# BIRDS-5_FM_-X_Panel_Ver2.net
KiCad netlist of a schematic drawn in EAGLE
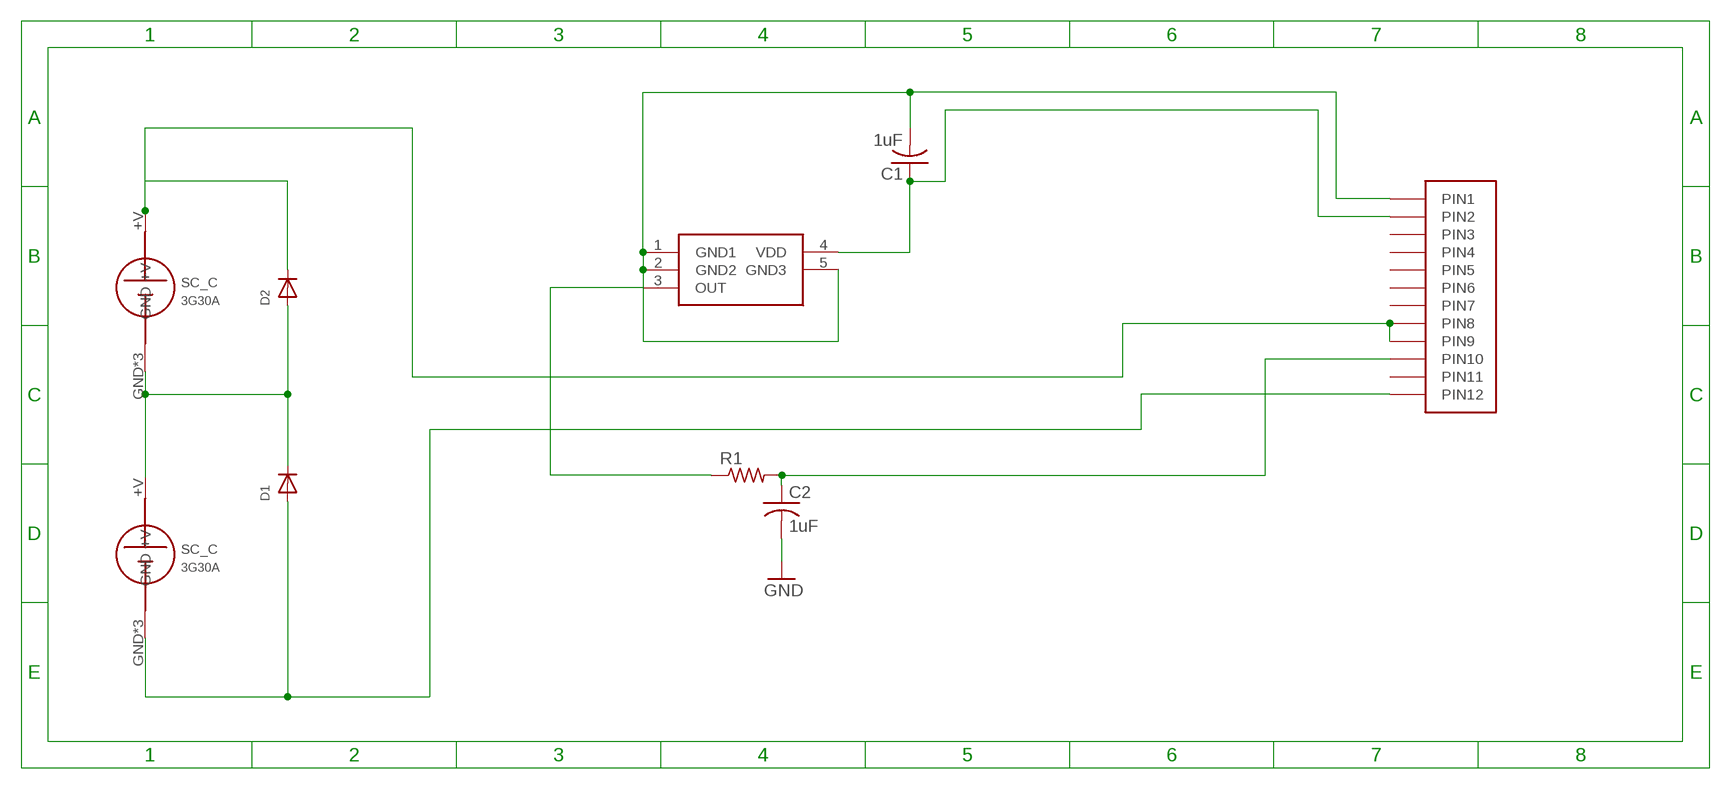
[diagram p0: schematic, sheet 1]

(export (version "E")
  (design (tool "Eeschema 10.0.6"))
  (components
    (comp (ref "C1")
      (value "1uF")
      (footprint "eagle-import:C0805")
      (libsource (lib "eagle-import") (part "C-USC0805"))
    )
    (comp (ref "C2")
      (value "1uF")
      (footprint "eagle-import:C0805")
      (libsource (lib "eagle-import") (part "C-USC0805"))
    )
    (comp (ref "D1")
      (value "DIODE_SOD-123FL")
      (footprint "eagle-import:SOD-123FL")
      (libsource (lib "eagle-import") (part "DIODE_SOD-123FL"))
    )
    (comp (ref "D2")
      (value "DIODE_SOD-123FL")
      (footprint "eagle-import:SOD-123FL")
      (libsource (lib "eagle-import") (part "DIODE_SOD-123FL"))
    )
    (comp (ref "R1")
      (value "R-US_R0402")
      (footprint "eagle-import:R0402")
      (libsource (lib "eagle-import") (part "R-US_R0402"))
    )
    (comp (ref "U$1")
      (value "HEADER12PIN")
      (footprint "eagle-import:HEADER12PIN")
      (libsource (lib "eagle-import") (part "HEADER12PIN"))
    )
    (comp (ref "U$3")
      (value "LMT84DCKT")
      (footprint "eagle-import:SOT65P210X110-5N")
      (fields (field (name "RS_PART_NUMBER") "8115860"))
      (libsource (lib "eagle-import") (part "LMT84DCKT"))
    )
    (comp (ref "U$4")
      (value "SC_C")
      (footprint "eagle-import:SC_C")
      (libsource (lib "eagle-import") (part "SC_C"))
    )
    (comp (ref "U$5")
      (value "SC_C")
      (footprint "eagle-import:SC_C")
      (libsource (lib "eagle-import") (part "SC_C"))
    )
  )
  (nets
    (net (code "1") (name "GND") (class "Default")
      (node (ref "C1") (pin "2") (pinfunction "2_2") (pintype "passive"))
      (node (ref "C2") (pin "2") (pinfunction "2_2") (pintype "passive"))
      (node (ref "D1") (pin "A") (pinfunction "A_A") (pintype "passive"))
      (node (ref "U$1") (pin "P1") (pinfunction "PIN1_P1") (pintype "bidirectional"))
      (node (ref "U$1") (pin "P12") (pinfunction "PIN12_P12") (pintype "bidirectional"))
      (node (ref "U$3") (pin "1") (pinfunction "GND1_1") (pintype "power_in"))
      (node (ref "U$3") (pin "2") (pinfunction "GND2_2") (pintype "power_in"))
      (node (ref "U$3") (pin "5") (pinfunction "GND3_5") (pintype "power_in"))
      (node (ref "U$5") (pin "GND") (pinfunction "GND_GND") (pintype "bidirectional"))
      (node (ref "U$5") (pin "GND1") (pinfunction "GND_GND1") (pintype "bidirectional"))
      (node (ref "U$5") (pin "GND2") (pinfunction "GND_GND2") (pintype "bidirectional"))
    )
    (net (code "2") (name "Net-(D1-PadC)") (class "Default")
      (node (ref "D1") (pin "C") (pinfunction "C_C") (pintype "passive"))
      (node (ref "D2") (pin "A") (pinfunction "A_A") (pintype "passive"))
      (node (ref "U$4") (pin "GND") (pinfunction "GND_GND") (pintype "bidirectional"))
      (node (ref "U$4") (pin "GND1") (pinfunction "GND_GND1") (pintype "bidirectional"))
      (node (ref "U$4") (pin "GND2") (pinfunction "GND_GND2") (pintype "bidirectional"))
      (node (ref "U$5") (pin "+V") (pinfunction "+V_+V") (pintype "bidirectional"))
    )
    (net (code "3") (name "Net-(U$1-PIN2)") (class "Default")
      (node (ref "C1") (pin "1") (pinfunction "1_1") (pintype "passive"))
      (node (ref "U$1") (pin "P2") (pinfunction "PIN2_P2") (pintype "bidirectional"))
      (node (ref "U$3") (pin "4") (pinfunction "VDD_4") (pintype "power_in"))
    )
    (net (code "4") (name "Net-(U$1-PIN8)") (class "Default")
      (node (ref "D2") (pin "C") (pinfunction "C_C") (pintype "passive"))
      (node (ref "U$1") (pin "P8") (pinfunction "PIN8_P8") (pintype "bidirectional"))
      (node (ref "U$1") (pin "P9") (pinfunction "PIN9_P9") (pintype "bidirectional"))
      (node (ref "U$4") (pin "+V") (pinfunction "+V_+V") (pintype "bidirectional"))
    )
    (net (code "5") (name "Net-(U$1-PIN10)") (class "Default")
      (node (ref "C2") (pin "1") (pinfunction "1_1") (pintype "passive"))
      (node (ref "R1") (pin "2") (pinfunction "2_2") (pintype "passive"))
      (node (ref "U$1") (pin "P10") (pinfunction "PIN10_P10") (pintype "bidirectional"))
    )
    (net (code "6") (name "Net-(U$3-OUT)") (class "Default")
      (node (ref "R1") (pin "1") (pinfunction "1_1") (pintype "passive"))
      (node (ref "U$3") (pin "3") (pinfunction "OUT_3") (pintype "output"))
    )
    (net (code "7") (name "unconnected-(U$1-PIN3-PadP3)") (class "Default")
      (node (ref "U$1") (pin "P3") (pinfunction "PIN3_P3") (pintype "bidirectional"))
    )
    (net (code "8") (name "unconnected-(U$1-PIN4-PadP4)") (class "Default")
      (node (ref "U$1") (pin "P4") (pinfunction "PIN4_P4") (pintype "bidirectional"))
    )
    (net (code "9") (name "unconnected-(U$1-PIN5-PadP5)") (class "Default")
      (node (ref "U$1") (pin "P5") (pinfunction "PIN5_P5") (pintype "bidirectional"))
    )
    (net (code "10") (name "unconnected-(U$1-PIN6-PadP6)") (class "Default")
      (node (ref "U$1") (pin "P6") (pinfunction "PIN6_P6") (pintype "bidirectional"))
    )
    (net (code "11") (name "unconnected-(U$1-PIN7-PadP7)") (class "Default")
      (node (ref "U$1") (pin "P7") (pinfunction "PIN7_P7") (pintype "bidirectional"))
    )
    (net (code "12") (name "unconnected-(U$1-PIN11-PadP11)") (class "Default")
      (node (ref "U$1") (pin "P11") (pinfunction "PIN11_P11") (pintype "bidirectional"))
    )
  )
)
